# SpinningDiscPCB.net
KiCad netlist of a schematic drawn in EAGLE
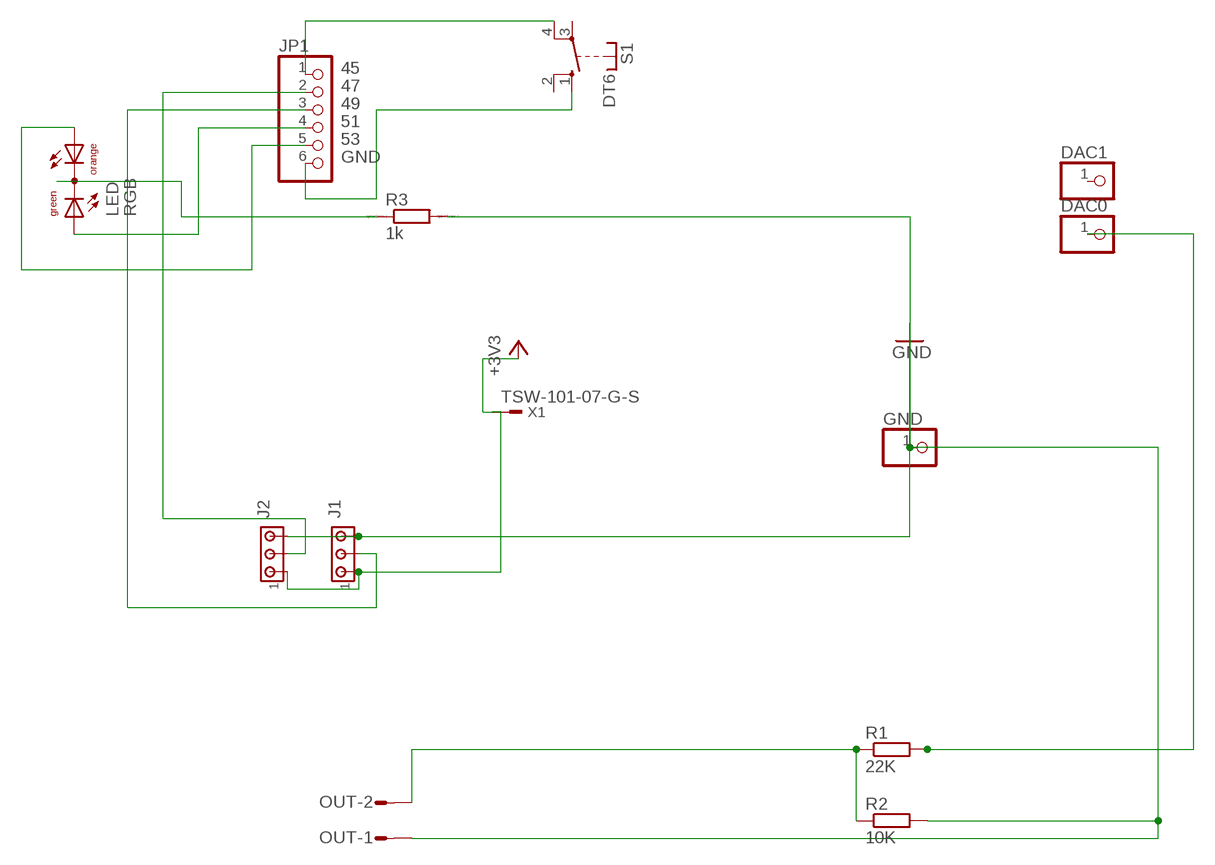
[diagram p0: schematic, sheet 1]

(export (version "E")
  (design (tool "Eeschema 10.0.6"))
  (components
    (comp (ref "DAC0")
      (value "PINHD-1X1")
      (footprint "eagle-import:1X01")
      (libsource (lib "eagle-import") (part "PINHD-1X1"))
    )
    (comp (ref "DAC1")
      (value "PINHD-1X1")
      (footprint "eagle-import:1X01")
      (libsource (lib "eagle-import") (part "PINHD-1X1"))
    )
    (comp (ref "GND")
      (value "PINHD-1X1")
      (footprint "eagle-import:1X01")
      (libsource (lib "eagle-import") (part "PINHD-1X1"))
    )
    (comp (ref "J1")
      (value "MTA03-100")
      (footprint "eagle-import:10X03MTA")
      (libsource (lib "eagle-import") (part "MTA03-100"))
    )
    (comp (ref "J2")
      (value "MTA03-100")
      (footprint "eagle-import:10X03MTA")
      (libsource (lib "eagle-import") (part "MTA03-100"))
    )
    (comp (ref "JP1")
      (value "PINHD-1X6")
      (footprint "eagle-import:1X06")
      (libsource (lib "eagle-import") (part "PINHD-1X6"))
    )
    (comp (ref "LED")
      (value "RGB")
      (footprint "eagle-import:TLUV5300")
      (libsource (lib "eagle-import") (part "TLUV5300"))
    )
    (comp (ref "OUT")
      (value "L02P")
      (footprint "eagle-import:L02P")
      (libsource (lib "eagle-import") (part "L02P"))
    )
    (comp (ref "R1")
      (value "22K")
      (footprint "eagle-import:0207_10")
      (libsource (lib "eagle-import") (part "R-EU_0207/10"))
    )
    (comp (ref "R2")
      (value "10K")
      (footprint "eagle-import:0207_10")
      (libsource (lib "eagle-import") (part "R-EU_0207/10"))
    )
    (comp (ref "R3")
      (value "1k")
      (footprint "eagle-import:0207_10")
      (libsource (lib "eagle-import") (part "R0207/10"))
    )
    (comp (ref "S1")
      (value "DT6")
      (footprint "eagle-import:DT6")
      (libsource (lib "eagle-import") (part "DT6"))
    )
    (comp (ref "X1")
      (value "TSW-101-07-G-S")
      (footprint "eagle-import:TSW-101-XX-G-S")
      (fields (field (name "MF") "Samtec Inc."))
      (libsource (lib "eagle-import") (part "TSW-101--G-S07"))
    )
  )
  (nets
    (net (code "1") (name "+3V3") (class "Default")
      (node (ref "J1") (pin "1") (pinfunction "1_1") (pintype "passive"))
      (node (ref "J2") (pin "1") (pinfunction "1_1") (pintype "passive"))
      (node (ref "X1") (pin "1") (pinfunction "1_1") (pintype "passive"))
    )
    (net (code "2") (name "/45") (class "Default")
      (node (ref "JP1") (pin "1") (pinfunction "1_1") (pintype "passive"))
      (node (ref "S1") (pin "4") (pinfunction "P_4") (pintype "passive"))
    )
    (net (code "3") (name "/47") (class "Default")
      (node (ref "J2") (pin "2") (pinfunction "2_2") (pintype "passive"))
      (node (ref "JP1") (pin "2") (pinfunction "2_2") (pintype "passive"))
    )
    (net (code "4") (name "/49") (class "Default")
      (node (ref "J1") (pin "2") (pinfunction "2_2") (pintype "passive"))
      (node (ref "JP1") (pin "3") (pinfunction "3_3") (pintype "passive"))
    )
    (net (code "5") (name "/51") (class "Default")
      (node (ref "JP1") (pin "4") (pinfunction "4_4") (pintype "passive"))
      (node (ref "LED") (pin "AG") (pinfunction "AG_AG") (pintype "passive"))
    )
    (net (code "6") (name "/53") (class "Default")
      (node (ref "JP1") (pin "5") (pinfunction "5_5") (pintype "passive"))
      (node (ref "LED") (pin "AO") (pinfunction "AO_AO") (pintype "passive"))
    )
    (net (code "7") (name "GND") (class "Default")
      (node (ref "GND") (pin "1") (pinfunction "1_1") (pintype "passive"))
      (node (ref "J1") (pin "3") (pinfunction "3_3") (pintype "passive"))
      (node (ref "J2") (pin "3") (pinfunction "3_3") (pintype "passive"))
      (node (ref "LED") (pin "CC") (pinfunction "CC_CC") (pintype "passive"))
      (node (ref "OUT") (pin "1") (pinfunction "S_1") (pintype "passive"))
      (node (ref "R2") (pin "2") (pinfunction "2_2") (pintype "passive"))
      (node (ref "R3") (pin "1") (pinfunction "1_1") (pintype "passive"))
      (node (ref "R3") (pin "2") (pinfunction "2_2") (pintype "passive"))
    )
    (net (code "8") (name "Net-(DAC0-Pad1)") (class "Default")
      (node (ref "DAC0") (pin "1") (pinfunction "1_1") (pintype "passive"))
      (node (ref "R1") (pin "2") (pinfunction "2_2") (pintype "passive"))
    )
    (net (code "9") (name "Net-(JP1-Pad6)") (class "Default")
      (node (ref "JP1") (pin "6") (pinfunction "6_6") (pintype "passive"))
      (node (ref "S1") (pin "1") (pinfunction "S_1") (pintype "passive"))
    )
    (net (code "10") (name "Net-(OUTB-S)") (class "Default")
      (node (ref "OUT") (pin "2") (pinfunction "S_2") (pintype "passive"))
      (node (ref "R1") (pin "1") (pinfunction "1_1") (pintype "passive"))
      (node (ref "R2") (pin "1") (pinfunction "1_1") (pintype "passive"))
    )
    (net (code "11") (name "unconnected-(DAC1-Pad1)") (class "Default")
      (node (ref "DAC1") (pin "1") (pinfunction "1_1") (pintype "passive"))
    )
    (net (code "12") (name "unconnected-(S1-P-Pad3)") (class "Default")
      (node (ref "S1") (pin "3") (pinfunction "P_3") (pintype "passive"))
    )
    (net (code "13") (name "unconnected-(S1-S-Pad2)") (class "Default")
      (node (ref "S1") (pin "2") (pinfunction "S_2") (pintype "passive"))
    )
  )
)
